# Flex.net
KiCad netlist of a schematic drawn in EAGLE
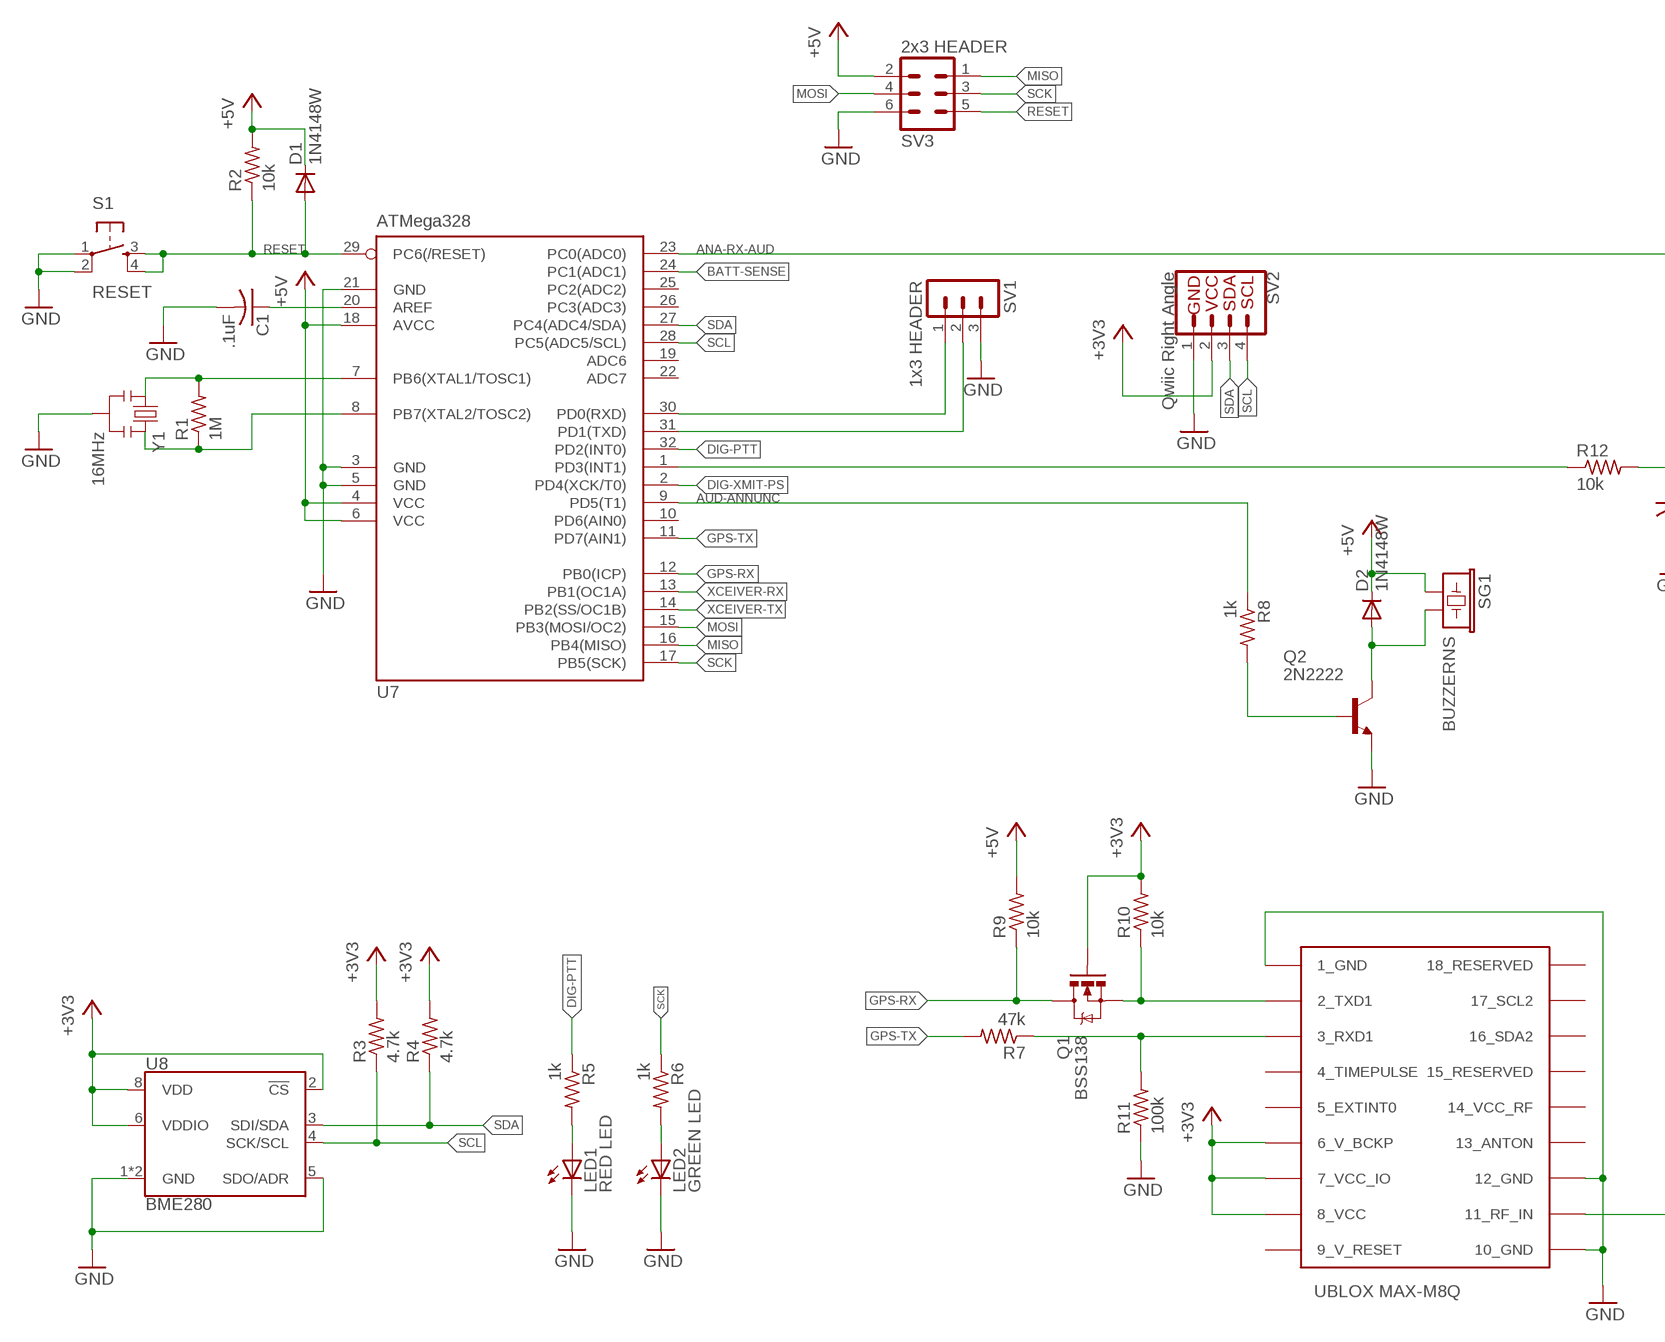
[diagram p0: schematic, sheet 1, part 1 of 2]
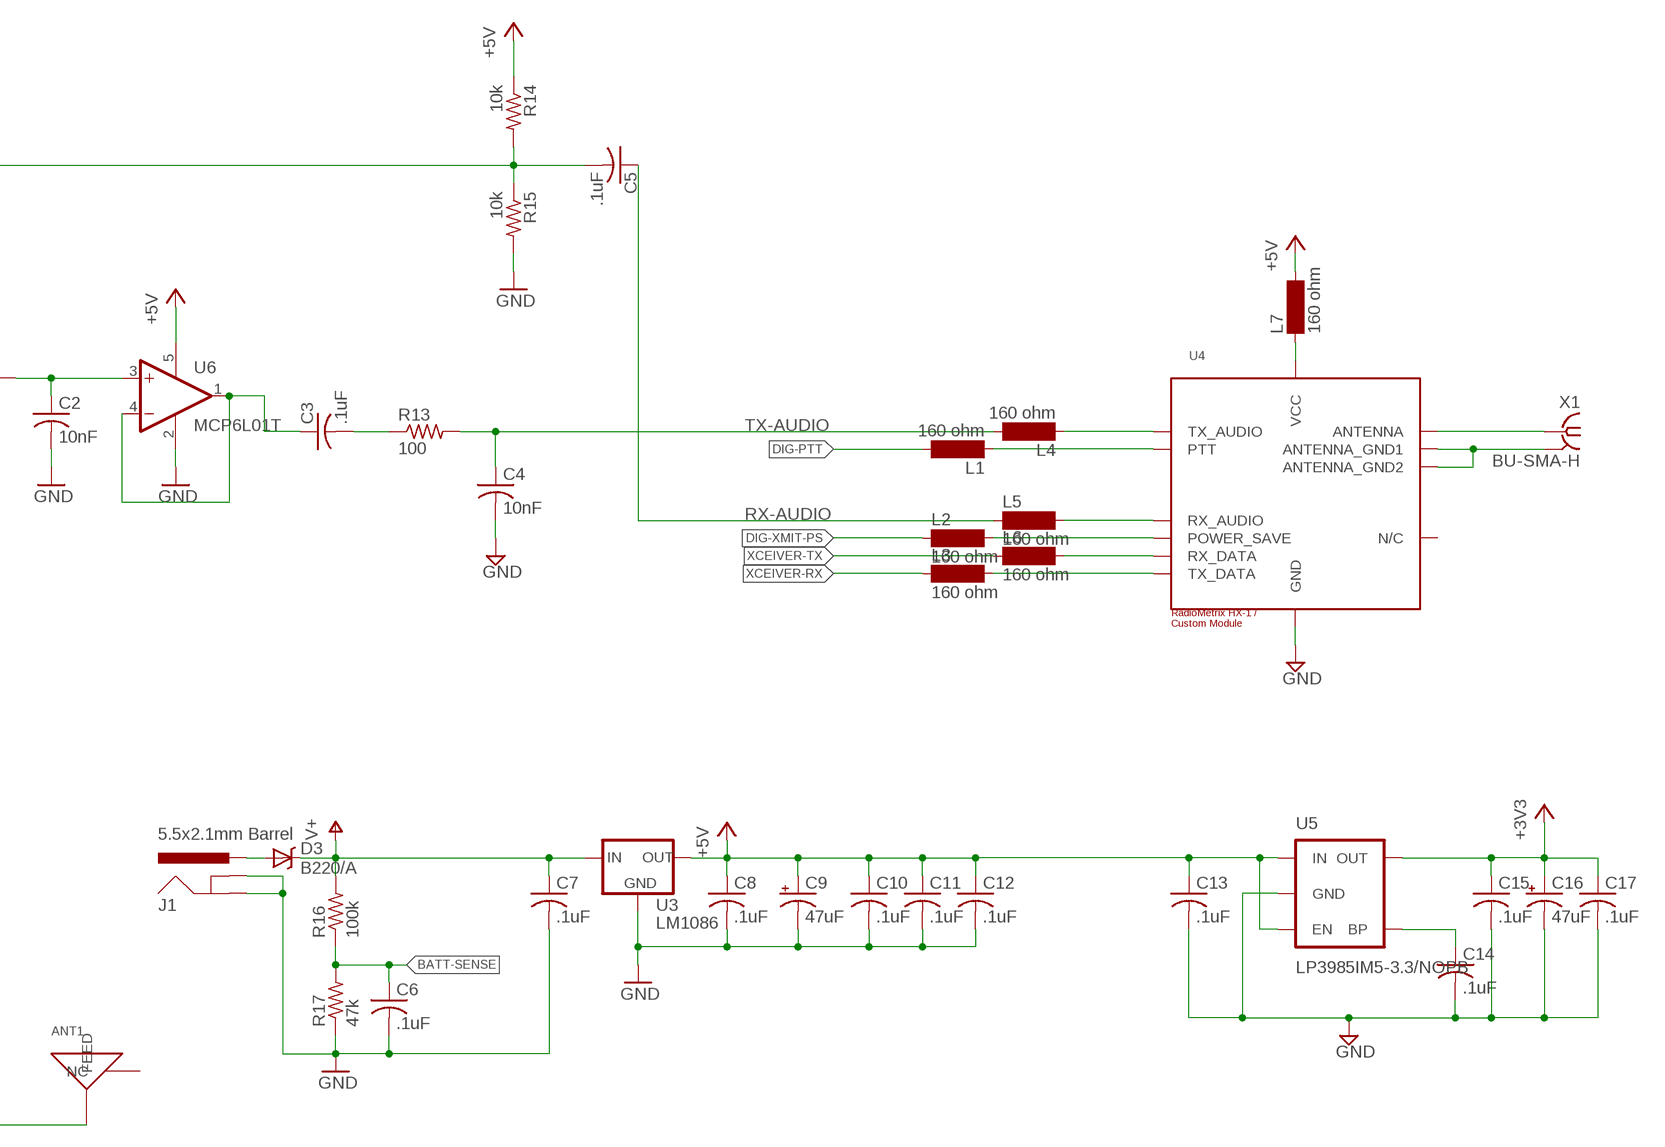
[diagram p1: schematic, sheet 1, part 2 of 2]

(export (version "E")
  (design (tool "Eeschema 10.0.6"))
  (components
    (comp (ref "ANT1")
      (value "GPS ANTENNA")
      (footprint "eagle-import:1575AT43A40")
      (libsource (lib "eagle-import") (part "GPS_ANT_SMDBAR"))
    )
    (comp (ref "C1")
      (value ".1uF")
      (footprint "eagle-import:C0805")
      (libsource (lib "eagle-import") (part "C-USC0805"))
    )
    (comp (ref "C2")
      (value "10nF")
      (footprint "eagle-import:C0805")
      (libsource (lib "eagle-import") (part "C-USC0805"))
    )
    (comp (ref "C3")
      (value ".1uF")
      (footprint "eagle-import:C0805")
      (libsource (lib "eagle-import") (part "C-USC0805"))
    )
    (comp (ref "C4")
      (value "10nF")
      (footprint "eagle-import:C0805")
      (libsource (lib "eagle-import") (part "C-USC0805"))
    )
    (comp (ref "C5")
      (value ".1uF")
      (footprint "eagle-import:C0805")
      (libsource (lib "eagle-import") (part "C-USC0805"))
    )
    (comp (ref "C6")
      (value ".1uF")
      (footprint "eagle-import:C0805")
      (libsource (lib "eagle-import") (part "C-USC0805"))
    )
    (comp (ref "C7")
      (value ".1uF")
      (footprint "eagle-import:C0805")
      (libsource (lib "eagle-import") (part "C-USC0805"))
    )
    (comp (ref "C8")
      (value ".1uF")
      (footprint "eagle-import:C0805")
      (libsource (lib "eagle-import") (part "C-USC0805"))
    )
    (comp (ref "C9")
      (value "47uF")
      (footprint "eagle-import:153CLV-0605")
      (libsource (lib "eagle-import") (part "CPOL-US153CLV-0605"))
    )
    (comp (ref "C10")
      (value ".1uF")
      (footprint "eagle-import:C0805")
      (libsource (lib "eagle-import") (part "C-USC0805"))
    )
    (comp (ref "C11")
      (value ".1uF")
      (footprint "eagle-import:C0805")
      (libsource (lib "eagle-import") (part "C-USC0805"))
    )
    (comp (ref "C12")
      (value ".1uF")
      (footprint "eagle-import:C0805")
      (libsource (lib "eagle-import") (part "C-USC0805"))
    )
    (comp (ref "C13")
      (value ".1uF")
      (footprint "eagle-import:C0805")
      (libsource (lib "eagle-import") (part "C-USC0805"))
    )
    (comp (ref "C14")
      (value ".1uF")
      (footprint "eagle-import:C0805")
      (libsource (lib "eagle-import") (part "C-USC0805"))
    )
    (comp (ref "C15")
      (value ".1uF")
      (footprint "eagle-import:C0805")
      (libsource (lib "eagle-import") (part "C-USC0805"))
    )
    (comp (ref "C16")
      (value "47uF")
      (footprint "eagle-import:153CLV-0605")
      (libsource (lib "eagle-import") (part "CPOL-US153CLV-0605"))
    )
    (comp (ref "C17")
      (value ".1uF")
      (footprint "eagle-import:C0805")
      (libsource (lib "eagle-import") (part "C-USC0805"))
    )
    (comp (ref "D1")
      (value "1N4148W")
      (footprint "eagle-import:SOD123")
      (libsource (lib "eagle-import") (part "DIODE-SOD123"))
    )
    (comp (ref "D2")
      (value "1N4148W")
      (footprint "eagle-import:SOD123")
      (libsource (lib "eagle-import") (part "DIODE-SOD123"))
    )
    (comp (ref "D3")
      (value "B220/A")
      (footprint "eagle-import:SMA-DIODE")
      (libsource (lib "eagle-import") (part "B340A"))
    )
    (comp (ref "J1")
      (value "5.5x2.1mm Barrel")
      (footprint "eagle-import:POWER_JACK_SMD")
      (libsource (lib "eagle-import") (part "POWER_JACKSMD"))
    )
    (comp (ref "L1")
      (value "160 ohm")
      (footprint "eagle-import:SM-1206")
      (libsource (lib "eagle-import") (part "SM-1206"))
    )
    (comp (ref "L2")
      (value "160 ohm")
      (footprint "eagle-import:SM-1206")
      (libsource (lib "eagle-import") (part "SM-1206"))
    )
    (comp (ref "L3")
      (value "160 ohm")
      (footprint "eagle-import:SM-1206")
      (libsource (lib "eagle-import") (part "SM-1206"))
    )
    (comp (ref "L4")
      (value "160 ohm")
      (footprint "eagle-import:SM-1206")
      (libsource (lib "eagle-import") (part "SM-1206"))
    )
    (comp (ref "L5")
      (value "160 ohm")
      (footprint "eagle-import:SM-1206")
      (libsource (lib "eagle-import") (part "SM-1206"))
    )
    (comp (ref "L6")
      (value "160 ohm")
      (footprint "eagle-import:SM-1206")
      (libsource (lib "eagle-import") (part "SM-1206"))
    )
    (comp (ref "L7")
      (value "160 ohm")
      (footprint "eagle-import:SM-1206")
      (libsource (lib "eagle-import") (part "SM-1206"))
    )
    (comp (ref "LED1")
      (value "RED LED")
      (footprint "eagle-import:CHIPLED_1206")
      (libsource (lib "eagle-import") (part "LEDCHIPLED_1206"))
    )
    (comp (ref "LED2")
      (value "GREEN LED")
      (footprint "eagle-import:CHIPLED_1206")
      (libsource (lib "eagle-import") (part "LEDCHIPLED_1206"))
    )
    (comp (ref "Q1")
      (value "BSS138")
      (footprint "eagle-import:SOT23")
      (libsource (lib "eagle-import") (part "MOSFET-NCHANNELBSS138"))
    )
    (comp (ref "Q2")
      (value "2N2222")
      (footprint "eagle-import:SOT23-BEC")
      (libsource (lib "eagle-import") (part "BC817SMD-16LT1"))
    )
    (comp (ref "R1")
      (value "1M")
      (footprint "eagle-import:R0805")
      (libsource (lib "eagle-import") (part "R-US_R0805"))
    )
    (comp (ref "R2")
      (value "10k")
      (footprint "eagle-import:R0805")
      (libsource (lib "eagle-import") (part "R-US_R0805"))
    )
    (comp (ref "R3")
      (value "4.7k")
      (footprint "eagle-import:R0805")
      (libsource (lib "eagle-import") (part "R-US_R0805"))
    )
    (comp (ref "R4")
      (value "4.7k")
      (footprint "eagle-import:R0805")
      (libsource (lib "eagle-import") (part "R-US_R0805"))
    )
    (comp (ref "R5")
      (value "1k")
      (footprint "eagle-import:R0805")
      (libsource (lib "eagle-import") (part "R-US_R0805"))
    )
    (comp (ref "R6")
      (value "1k")
      (footprint "eagle-import:R0805")
      (libsource (lib "eagle-import") (part "R-US_R0805"))
    )
    (comp (ref "R7")
      (value "47k")
      (footprint "eagle-import:R0805")
      (libsource (lib "eagle-import") (part "R-US_R0805"))
    )
    (comp (ref "R8")
      (value "1k")
      (footprint "eagle-import:R0805")
      (libsource (lib "eagle-import") (part "R-US_R0805"))
    )
    (comp (ref "R9")
      (value "10k")
      (footprint "eagle-import:R0805")
      (libsource (lib "eagle-import") (part "R-US_R0805"))
    )
    (comp (ref "R10")
      (value "10k")
      (footprint "eagle-import:R0805")
      (libsource (lib "eagle-import") (part "R-US_R0805"))
    )
    (comp (ref "R11")
      (value "100k")
      (footprint "eagle-import:R0805")
      (libsource (lib "eagle-import") (part "R-US_R0805"))
    )
    (comp (ref "R12")
      (value "10k")
      (footprint "eagle-import:R0805")
      (libsource (lib "eagle-import") (part "R-US_R0805"))
    )
    (comp (ref "R13")
      (value "100")
      (footprint "eagle-import:R0805")
      (libsource (lib "eagle-import") (part "R-US_R0805"))
    )
    (comp (ref "R14")
      (value "10k")
      (footprint "eagle-import:R0805")
      (libsource (lib "eagle-import") (part "R-US_R0805"))
    )
    (comp (ref "R15")
      (value "10k")
      (footprint "eagle-import:R0805")
      (libsource (lib "eagle-import") (part "R-US_R0805"))
    )
    (comp (ref "R16")
      (value "100k")
      (footprint "eagle-import:R0805")
      (libsource (lib "eagle-import") (part "R-US_R0805"))
    )
    (comp (ref "R17")
      (value "47k")
      (footprint "eagle-import:R0805")
      (libsource (lib "eagle-import") (part "R-US_R0805"))
    )
    (comp (ref "S1")
      (value "RESET")
      (footprint "eagle-import:TACTILE_SWITCH_SMD")
      (libsource (lib "eagle-import") (part "TAC_SWITCHSMD"))
    )
    (comp (ref "SG1")
      (value "BUZZERNS")
      (footprint "eagle-import:BUZZER-12MM-NS")
      (libsource (lib "eagle-import") (part "BUZZERNS"))
    )
    (comp (ref "SV1")
      (value "1x3 HEADER")
      (footprint "eagle-import:MA03-1")
      (libsource (lib "eagle-import") (part "MA03-1"))
    )
    (comp (ref "SV2")
      (value "Qwiic Right Angle")
      (footprint "eagle-import:1X04_1MM_RA")
      (libsource (lib "eagle-import") (part "I2C_STANDARDQWIIC"))
    )
    (comp (ref "SV3")
      (value "2x3 HEADER")
      (footprint "eagle-import:MA03-2")
      (libsource (lib "eagle-import") (part "MA03-2"))
    )
    (comp (ref "U2")
      (value "UBLOX_MAX")
      (footprint "eagle-import:UBLOX_MAX")
      (fields (field (name "ALT-PART") "UBLOX MAX-M8Q"))
      (libsource (lib "eagle-import") (part "UBLOX_MAX"))
    )
    (comp (ref "U3")
      (value "LM1086")
      (footprint "eagle-import:TO263")
      (libsource (lib "eagle-import") (part "LM1086TO263"))
    )
    (comp (ref "U4")
      (value "RADIOMETRIX-HX1-CUSTOM")
      (footprint "eagle-import:RADIOMETRIX-HX1-CUSTOM")
      (libsource (lib "eagle-import") (part "RADIOMETRIX-HX1-CUSTOM"))
    )
    (comp (ref "U5")
      (value "LP3985IM5-3.3/NOPB")
      (footprint "eagle-import:SOT23-5")
      (libsource (lib "eagle-import") (part "V_REG_LDOSMD"))
    )
    (comp (ref "U6")
      (value "MCP6L01T")
      (footprint "eagle-import:SOT23-5")
      (libsource (lib "eagle-import") (part "OPA725DBV"))
    )
    (comp (ref "U7")
      (value "ATMega328")
      (footprint "eagle-import:TQFP32-08")
      (fields (field (name "MPN") "ATMEGA8-16AU"))
      (libsource (lib "eagle-import") (part "MEGA8-AI"))
    )
    (comp (ref "U8")
      (value "BME280")
      (footprint "eagle-import:LGA-8-2.5X2.5")
      (libsource (lib "eagle-import") (part "BME280"))
    )
    (comp (ref "X1")
      (value "BU-SMA-H")
      (footprint "eagle-import:BU-SMA-H")
      (libsource (lib "eagle-import") (part "BU-SMA-H"))
    )
    (comp (ref "Y1")
      (value "16MHz")
      (footprint "eagle-import:RESONATOR-SMD")
      (libsource (lib "eagle-import") (part "RESONATOR16MHZ"))
    )
  )
  (nets
    (net (code "1") (name "+3V3") (class "Default")
      (node (ref "C15") (pin "1") (pinfunction "1_1") (pintype "passive"))
      (node (ref "C16") (pin "+") (pinfunction "+_+") (pintype "passive"))
      (node (ref "C17") (pin "1") (pinfunction "1_1") (pintype "passive"))
      (node (ref "Q1") (pin "1") (pinfunction "G_1") (pintype "passive"))
      (node (ref "R10") (pin "2") (pinfunction "2_2") (pintype "passive"))
      (node (ref "R3") (pin "2") (pinfunction "2_2") (pintype "passive"))
      (node (ref "R4") (pin "2") (pinfunction "2_2") (pintype "passive"))
      (node (ref "SV2") (pin "2") (pinfunction "2_2") (pintype "power_in"))
      (node (ref "U2") (pin "6_V_BCKP") (pinfunction "6_V_BCKP_6_V_BCKP") (pintype "bidirectional"))
      (node (ref "U2") (pin "7_VCC_IO") (pinfunction "7_VCC_IO_7_VCC_IO") (pintype "power_in"))
      (node (ref "U2") (pin "8_VCC") (pinfunction "8_VCC_8_VCC") (pintype "power_in"))
      (node (ref "U5") (pin "5") (pinfunction "OUT_5") (pintype "passive"))
      (node (ref "U8") (pin "2") (pinfunction "~{CS}_2") (pintype "bidirectional"))
      (node (ref "U8") (pin "6") (pinfunction "VDDIO_6") (pintype "bidirectional"))
      (node (ref "U8") (pin "8") (pinfunction "VDD_8") (pintype "bidirectional"))
    )
    (net (code "2") (name "+5V") (class "Default")
      (node (ref "C10") (pin "1") (pinfunction "1_1") (pintype "passive"))
      (node (ref "C11") (pin "1") (pinfunction "1_1") (pintype "passive"))
      (node (ref "C12") (pin "1") (pinfunction "1_1") (pintype "passive"))
      (node (ref "C13") (pin "1") (pinfunction "1_1") (pintype "passive"))
      (node (ref "C8") (pin "1") (pinfunction "1_1") (pintype "passive"))
      (node (ref "C9") (pin "+") (pinfunction "+_+") (pintype "passive"))
      (node (ref "D1") (pin "C") (pinfunction "C_C") (pintype "passive"))
      (node (ref "D2") (pin "C") (pinfunction "C_C") (pintype "passive"))
      (node (ref "L7") (pin "2") (pinfunction "2_2") (pintype "passive"))
      (node (ref "R14") (pin "1") (pinfunction "1_1") (pintype "passive"))
      (node (ref "R2") (pin "2") (pinfunction "2_2") (pintype "passive"))
      (node (ref "R9") (pin "2") (pinfunction "2_2") (pintype "passive"))
      (node (ref "SG1") (pin "+") (pinfunction "1_+") (pintype "passive"))
      (node (ref "SV3") (pin "2") (pinfunction "2_2") (pintype "passive"))
      (node (ref "U3") (pin "2") (pinfunction "OUT_2") (pintype "passive"))
      (node (ref "U5") (pin "1") (pinfunction "IN_1") (pintype "input"))
      (node (ref "U5") (pin "3") (pinfunction "EN_3") (pintype "input"))
      (node (ref "U6") (pin "5") (pinfunction "V+_5") (pintype "power_in"))
      (node (ref "U7") (pin "18") (pinfunction "AVCC_18") (pintype "power_in"))
      (node (ref "U7") (pin "4") (pinfunction "VCC_4") (pintype "power_in"))
      (node (ref "U7") (pin "6") (pinfunction "VCC_6") (pintype "power_in"))
    )
    (net (code "3") (name "/9_V_RESET") (class "Default")
      (node (ref "U2") (pin "9_V_RESET") (pinfunction "9_V_RESET_9_V_RESET") (pintype "power_in"))
    )
    (net (code "4") (name "/ANA-RX-AUD") (class "Default")
      (node (ref "C5") (pin "2") (pinfunction "2_2") (pintype "passive"))
      (node (ref "R14") (pin "2") (pinfunction "2_2") (pintype "passive"))
      (node (ref "R15") (pin "1") (pinfunction "1_1") (pintype "passive"))
      (node (ref "U7") (pin "23") (pinfunction "PC0(ADC0)_23") (pintype "bidirectional"))
    )
    (net (code "5") (name "/AUD-ANNUNC") (class "Default")
      (node (ref "R8") (pin "1") (pinfunction "1_1") (pintype "passive"))
      (node (ref "U7") (pin "9") (pinfunction "PD5(T1)_9") (pintype "bidirectional"))
    )
    (net (code "6") (name "/RX-AUDIO") (class "Default")
      (node (ref "C5") (pin "1") (pinfunction "1_1") (pintype "passive"))
      (node (ref "L5") (pin "1") (pinfunction "1_1") (pintype "passive"))
    )
    (net (code "7") (name "/TX-AUDIO") (class "Default")
      (node (ref "C3") (pin "2") (pinfunction "2_2") (pintype "passive"))
      (node (ref "R13") (pin "1") (pinfunction "1_1") (pintype "passive"))
    )
    (net (code "8") (name "BATT-SENSE") (class "Default")
      (node (ref "C6") (pin "1") (pinfunction "1_1") (pintype "passive"))
      (node (ref "R16") (pin "1") (pinfunction "1_1") (pintype "passive"))
      (node (ref "R17") (pin "2") (pinfunction "2_2") (pintype "passive"))
      (node (ref "U7") (pin "24") (pinfunction "PC1(ADC1)_24") (pintype "bidirectional"))
    )
    (net (code "9") (name "DIG-PTT") (class "Default")
      (node (ref "L1") (pin "2") (pinfunction "2_2") (pintype "passive"))
      (node (ref "R5") (pin "1") (pinfunction "1_1") (pintype "passive"))
      (node (ref "U7") (pin "32") (pinfunction "PD2(INT0)_32") (pintype "bidirectional"))
    )
    (net (code "10") (name "DIG-XMIT-PS") (class "Default")
      (node (ref "L2") (pin "1") (pinfunction "1_1") (pintype "passive"))
      (node (ref "U7") (pin "2") (pinfunction "PD4(XCK/T0)_2") (pintype "bidirectional"))
    )
    (net (code "11") (name "GND") (class "Default")
      (node (ref "C1") (pin "2") (pinfunction "2_2") (pintype "passive"))
      (node (ref "C10") (pin "2") (pinfunction "2_2") (pintype "passive"))
      (node (ref "C11") (pin "2") (pinfunction "2_2") (pintype "passive"))
      (node (ref "C12") (pin "2") (pinfunction "2_2") (pintype "passive"))
      (node (ref "C13") (pin "2") (pinfunction "2_2") (pintype "passive"))
      (node (ref "C14") (pin "2") (pinfunction "2_2") (pintype "passive"))
      (node (ref "C15") (pin "2") (pinfunction "2_2") (pintype "passive"))
      (node (ref "C16") (pin "-") (pinfunction "-_-") (pintype "passive"))
      (node (ref "C17") (pin "2") (pinfunction "2_2") (pintype "passive"))
      (node (ref "C2") (pin "2") (pinfunction "2_2") (pintype "passive"))
      (node (ref "C4") (pin "2") (pinfunction "2_2") (pintype "passive"))
      (node (ref "C6") (pin "2") (pinfunction "2_2") (pintype "passive"))
      (node (ref "C7") (pin "2") (pinfunction "2_2") (pintype "passive"))
      (node (ref "C8") (pin "2") (pinfunction "2_2") (pintype "passive"))
      (node (ref "C9") (pin "-") (pinfunction "-_-") (pintype "passive"))
      (node (ref "J1") (pin "GND") (pinfunction "GNDBREAK_GND") (pintype "bidirectional"))
      (node (ref "J1") (pin "P$4") (pinfunction "GND_P$4") (pintype "bidirectional"))
      (node (ref "LED1") (pin "C") (pinfunction "C_C") (pintype "passive"))
      (node (ref "LED2") (pin "C") (pinfunction "C_C") (pintype "passive"))
      (node (ref "Q2") (pin "E") (pinfunction "E_E") (pintype "passive"))
      (node (ref "R11") (pin "1") (pinfunction "1_1") (pintype "passive"))
      (node (ref "R15") (pin "2") (pinfunction "2_2") (pintype "passive"))
      (node (ref "R17") (pin "1") (pinfunction "1_1") (pintype "passive"))
      (node (ref "S1") (pin "1") (pinfunction "1_1") (pintype "passive"))
      (node (ref "S1") (pin "2") (pinfunction "2_2") (pintype "passive"))
      (node (ref "SV1") (pin "3") (pinfunction "3_3") (pintype "passive"))
      (node (ref "SV2") (pin "1") (pinfunction "1_1") (pintype "power_in"))
      (node (ref "SV3") (pin "6") (pinfunction "6_6") (pintype "passive"))
      (node (ref "U2") (pin "10_GND") (pinfunction "10_GND_10_GND") (pintype "power_in"))
      (node (ref "U2") (pin "12_GND") (pinfunction "12_GND_12_GND") (pintype "power_in"))
      (node (ref "U2") (pin "1_GND") (pinfunction "1_GND_1_GND") (pintype "power_in"))
      (node (ref "U3") (pin "1") (pinfunction "GND_1") (pintype "input"))
      (node (ref "U4") (pin "GND") (pinfunction "GND_GND") (pintype "power_in"))
      (node (ref "U5") (pin "2") (pinfunction "GND_2") (pintype "input"))
      (node (ref "U6") (pin "2") (pinfunction "V-_2") (pintype "power_in"))
      (node (ref "U7") (pin "21") (pinfunction "GND_21") (pintype "power_in"))
      (node (ref "U7") (pin "3") (pinfunction "GND_3") (pintype "power_in"))
      (node (ref "U7") (pin "5") (pinfunction "GND_5") (pintype "power_in"))
      (node (ref "U8") (pin "1") (pinfunction "GND_1") (pintype "bidirectional"))
      (node (ref "U8") (pin "5") (pinfunction "SDO/ADR_5") (pintype "bidirectional"))
      (node (ref "U8") (pin "7") (pinfunction "GND_7") (pintype "bidirectional"))
      (node (ref "Y1") (pin "2") (pinfunction "2_2") (pintype "passive"))
    )
    (net (code "12") (name "GPS-RX") (class "Default")
      (node (ref "Q1") (pin "3") (pinfunction "D_3") (pintype "passive"))
      (node (ref "R9") (pin "1") (pinfunction "1_1") (pintype "passive"))
      (node (ref "U7") (pin "12") (pinfunction "PB0(ICP)_12") (pintype "bidirectional"))
    )
    (net (code "13") (name "GPS-TX") (class "Default")
      (node (ref "R7") (pin "2") (pinfunction "2_2") (pintype "passive"))
      (node (ref "U7") (pin "11") (pinfunction "PD7(AIN1)_11") (pintype "bidirectional"))
    )
    (net (code "14") (name "MISO") (class "Default")
      (node (ref "SV3") (pin "1") (pinfunction "1_1") (pintype "passive"))
      (node (ref "U7") (pin "16") (pinfunction "PB4(MISO)_16") (pintype "bidirectional"))
    )
    (net (code "15") (name "MOSI") (class "Default")
      (node (ref "SV3") (pin "4") (pinfunction "4_4") (pintype "passive"))
      (node (ref "U7") (pin "15") (pinfunction "PB3(MOSI/OC2)_15") (pintype "bidirectional"))
    )
    (net (code "16") (name "Net-(ANT1-PadFEED)") (class "Default")
      (node (ref "ANT1") (pin "FEED") (pinfunction "FEED_FEED") (pintype "bidirectional"))
      (node (ref "U2") (pin "11_RF_IN") (pinfunction "11_RF_IN_11_RF_IN") (pintype "bidirectional"))
    )
    (net (code "17") (name "Net-(C4-Pad1)") (class "Default")
      (node (ref "C4") (pin "1") (pinfunction "1_1") (pintype "passive"))
      (node (ref "L4") (pin "2") (pinfunction "2_2") (pintype "passive"))
      (node (ref "R13") (pin "2") (pinfunction "2_2") (pintype "passive"))
    )
    (net (code "18") (name "Net-(J1-PWR)") (class "Default")
      (node (ref "D3") (pin "A") (pinfunction "A_A") (pintype "passive"))
      (node (ref "J1") (pin "VIN0") (pinfunction "PWR_VIN0") (pintype "bidirectional"))
    )
    (net (code "19") (name "Net-(L1-Pad1)") (class "Default")
      (node (ref "L1") (pin "1") (pinfunction "1_1") (pintype "passive"))
      (node (ref "U4") (pin "PTT") (pinfunction "PTT_PTT") (pintype "input"))
    )
    (net (code "20") (name "Net-(L2-Pad2)") (class "Default")
      (node (ref "L2") (pin "2") (pinfunction "2_2") (pintype "passive"))
      (node (ref "U4") (pin "POWER_SAVE") (pinfunction "POWER_SAVE_POWER_SAVE") (pintype "input"))
    )
    (net (code "21") (name "Net-(L3-Pad2)") (class "Default")
      (node (ref "L3") (pin "2") (pinfunction "2_2") (pintype "passive"))
      (node (ref "U4") (pin "TX_DATA") (pinfunction "TX_DATA_TX_DATA") (pintype "output"))
    )
    (net (code "22") (name "Net-(L4-Pad1)") (class "Default")
      (node (ref "L4") (pin "1") (pinfunction "1_1") (pintype "passive"))
      (node (ref "U4") (pin "TX_AUDIO") (pinfunction "TX_AUDIO_TX_AUDIO") (pintype "input"))
    )
    (net (code "23") (name "Net-(L5-Pad2)") (class "Default")
      (node (ref "L5") (pin "2") (pinfunction "2_2") (pintype "passive"))
      (node (ref "U4") (pin "RX_AUDIO") (pinfunction "RX_AUDIO_RX_AUDIO") (pintype "output"))
    )
    (net (code "24") (name "Net-(L6-Pad2)") (class "Default")
      (node (ref "L6") (pin "2") (pinfunction "2_2") (pintype "passive"))
      (node (ref "U4") (pin "RX_DATA") (pinfunction "RX_DATA_RX_DATA") (pintype "input"))
    )
    (net (code "25") (name "Net-(L7-Pad1)") (class "Default")
      (node (ref "L7") (pin "1") (pinfunction "1_1") (pintype "passive"))
      (node (ref "U4") (pin "VCC") (pinfunction "VCC_VCC") (pintype "power_in"))
    )
    (net (code "26") (name "Net-(LED1-PadA)") (class "Default")
      (node (ref "LED1") (pin "A") (pinfunction "A_A") (pintype "passive"))
      (node (ref "R5") (pin "2") (pinfunction "2_2") (pintype "passive"))
    )
    (net (code "27") (name "Net-(LED2-PadA)") (class "Default")
      (node (ref "LED2") (pin "A") (pinfunction "A_A") (pintype "passive"))
      (node (ref "R6") (pin "2") (pinfunction "2_2") (pintype "passive"))
    )
    (net (code "28") (name "Net-(Q1-S)") (class "Default")
      (node (ref "Q1") (pin "2") (pinfunction "S_2") (pintype "passive"))
      (node (ref "R10") (pin "1") (pinfunction "1_1") (pintype "passive"))
      (node (ref "U2") (pin "2_TXD1") (pinfunction "2_TXD1_2_TXD1") (pintype "bidirectional"))
    )
    (net (code "29") (name "Net-(Q2-PadB)") (class "Default")
      (node (ref "Q2") (pin "B") (pinfunction "B_B") (pintype "passive"))
      (node (ref "R8") (pin "2") (pinfunction "2_2") (pintype "passive"))
    )
    (net (code "30") (name "Net-(R11-Pad2)") (class "Default")
      (node (ref "R11") (pin "2") (pinfunction "2_2") (pintype "passive"))
      (node (ref "R7") (pin "1") (pinfunction "1_1") (pintype "passive"))
      (node (ref "U2") (pin "3_RXD1") (pinfunction "3_RXD1_3_RXD1") (pintype "bidirectional"))
    )
    (net (code "31") (name "Net-(SG1-2)") (class "Default")
      (node (ref "D2") (pin "A") (pinfunction "A_A") (pintype "passive"))
      (node (ref "Q2") (pin "C") (pinfunction "C_C") (pintype "passive"))
      (node (ref "SG1") (pin "-") (pinfunction "2_-") (pintype "passive"))
    )
    (net (code "32") (name "Net-(U4-PadANTENNA)") (class "Default")
      (node (ref "U4") (pin "ANTENNA") (pinfunction "ANTENNA_ANTENNA") (pintype "bidirectional"))
      (node (ref "X1") (pin "1") (pinfunction "1_1") (pintype "passive"))
    )
    (net (code "33") (name "Net-(U4-PadANTENNA_GND1)") (class "Default")
      (node (ref "U4") (pin "ANTENNA_GND1") (pinfunction "ANTENNA_GND1_ANTENNA_GND1") (pintype "bidirectional"))
      (node (ref "U4") (pin "ANTENNA_GND2") (pinfunction "ANTENNA_GND2_ANTENNA_GND2") (pintype "bidirectional"))
      (node (ref "X1") (pin "2") (pinfunction "2_2") (pintype "passive"))
      (node (ref "X1") (pin "3") (pinfunction "2_3") (pintype "passive"))
      (node (ref "X1") (pin "4") (pinfunction "2_4") (pintype "passive"))
      (node (ref "X1") (pin "5") (pinfunction "2_5") (pintype "passive"))
    )
    (net (code "34") (name "Net-(U5-BP)") (class "Default")
      (node (ref "C14") (pin "1") (pinfunction "1_1") (pintype "passive"))
      (node (ref "U5") (pin "4") (pinfunction "BP_4") (pintype "input"))
    )
    (net (code "35") (name "Net-(U6-+IN)") (class "Default")
      (node (ref "C2") (pin "1") (pinfunction "1_1") (pintype "passive"))
      (node (ref "R12") (pin "2") (pinfunction "2_2") (pintype "passive"))
      (node (ref "U6") (pin "3") (pinfunction "+IN_3") (pintype "input"))
    )
    (net (code "36") (name "Net-(U6--IN)") (class "Default")
      (node (ref "C3") (pin "1") (pinfunction "1_1") (pintype "passive"))
      (node (ref "U6") (pin "1") (pinfunction "OUT_1") (pintype "output"))
      (node (ref "U6") (pin "4") (pinfunction "-IN_4") (pintype "input"))
    )
    (net (code "37") (name "Net-(U7-AREF)") (class "Default")
      (node (ref "C1") (pin "1") (pinfunction "1_1") (pintype "passive"))
      (node (ref "U7") (pin "20") (pinfunction "AREF_20") (pintype "passive"))
    )
    (net (code "38") (name "Net-(U7-PB6(XTAL1{slash}TOSC1))") (class "Default")
      (node (ref "R1") (pin "2") (pinfunction "2_2") (pintype "passive"))
      (node (ref "U7") (pin "7") (pinfunction "PB6(XTAL1/TOSC1)_7") (pintype "bidirectional"))
      (node (ref "Y1") (pin "1") (pinfunction "1_1") (pintype "passive"))
    )
    (net (code "39") (name "Net-(U7-PB7(XTAL2{slash}TOSC2))") (class "Default")
      (node (ref "R1") (pin "1") (pinfunction "1_1") (pintype "passive"))
      (node (ref "U7") (pin "8") (pinfunction "PB7(XTAL2/TOSC2)_8") (pintype "bidirectional"))
      (node (ref "Y1") (pin "3") (pinfunction "3_3") (pintype "passive"))
    )
    (net (code "40") (name "Net-(U7-PD0(RXD))") (class "Default")
      (node (ref "SV1") (pin "1") (pinfunction "1_1") (pintype "passive"))
      (node (ref "U7") (pin "30") (pinfunction "PD0(RXD)_30") (pintype "bidirectional"))
    )
    (net (code "41") (name "Net-(U7-PD1(TXD))") (class "Default")
      (node (ref "SV1") (pin "2") (pinfunction "2_2") (pintype "passive"))
      (node (ref "U7") (pin "31") (pinfunction "PD1(TXD)_31") (pintype "bidirectional"))
    )
    (net (code "42") (name "Net-(U7-PD3(INT1))") (class "Default")
      (node (ref "R12") (pin "1") (pinfunction "1_1") (pintype "passive"))
      (node (ref "U7") (pin "1") (pinfunction "PD3(INT1)_1") (pintype "bidirectional"))
    )
    (net (code "43") (name "RESET") (class "Default")
      (node (ref "D1") (pin "A") (pinfunction "A_A") (pintype "passive"))
      (node (ref "R2") (pin "1") (pinfunction "1_1") (pintype "passive"))
      (node (ref "S1") (pin "3") (pinfunction "3_3") (pintype "passive"))
      (node (ref "S1") (pin "4") (pinfunction "4_4") (pintype "passive"))
      (node (ref "SV3") (pin "5") (pinfunction "5_5") (pintype "passive"))
      (node (ref "U7") (pin "29") (pinfunction "PC6(/RESET)_29") (pintype "bidirectional"))
    )
    (net (code "44") (name "SCK") (class "Default")
      (node (ref "R6") (pin "1") (pinfunction "1_1") (pintype "passive"))
      (node (ref "SV3") (pin "3") (pinfunction "3_3") (pintype "passive"))
      (node (ref "U7") (pin "17") (pinfunction "PB5(SCK)_17") (pintype "bidirectional"))
    )
    (net (code "45") (name "SCL") (class "Default")
      (node (ref "R3") (pin "1") (pinfunction "1_1") (pintype "passive"))
      (node (ref "SV2") (pin "4") (pinfunction "4_4") (pintype "passive"))
      (node (ref "U7") (pin "28") (pinfunction "PC5(ADC5/SCL)_28") (pintype "bidirectional"))
      (node (ref "U8") (pin "4") (pinfunction "SCK/SCL_4") (pintype "bidirectional"))
    )
    (net (code "46") (name "SDA") (class "Default")
      (node (ref "R4") (pin "1") (pinfunction "1_1") (pintype "passive"))
      (node (ref "SV2") (pin "3") (pinfunction "3_3") (pintype "passive"))
      (node (ref "U7") (pin "27") (pinfunction "PC4(ADC4/SDA)_27") (pintype "bidirectional"))
      (node (ref "U8") (pin "3") (pinfunction "SDI/SDA_3") (pintype "bidirectional"))
    )
    (net (code "47") (name "V+") (class "Default")
      (node (ref "C7") (pin "1") (pinfunction "1_1") (pintype "passive"))
      (node (ref "D3") (pin "C") (pinfunction "C_C") (pintype "passive"))
      (node (ref "R16") (pin "2") (pinfunction "2_2") (pintype "passive"))
      (node (ref "U3") (pin "3") (pinfunction "IN_3") (pintype "input"))
    )
    (net (code "48") (name "XCEIVER-RX") (class "Default")
      (node (ref "L3") (pin "1") (pinfunction "1_1") (pintype "passive"))
      (node (ref "U7") (pin "13") (pinfunction "PB1(OC1A)_13") (pintype "bidirectional"))
    )
    (net (code "49") (name "XCEIVER-TX") (class "Default")
      (node (ref "L6") (pin "1") (pinfunction "1_1") (pintype "passive"))
      (node (ref "U7") (pin "14") (pinfunction "PB2(SS/OC1B)_14") (pintype "bidirectional"))
    )
    (net (code "50") (name "unconnected-(ANT1-PadNC)") (class "Default")
      (node (ref "ANT1") (pin "NC") (pinfunction "NC_NC") (pintype "bidirectional"))
    )
    (net (code "51") (name "unconnected-(U2-Pad4_TIMEPULSE)") (class "Default")
      (node (ref "U2") (pin "4_TIMEPULSE") (pinfunction "4_TIMEPULSE_4_TIMEPULSE") (pintype "bidirectional"))
    )
    (net (code "52") (name "unconnected-(U2-Pad5_EXTINT0)") (class "Default")
      (node (ref "U2") (pin "5_EXTINT0") (pinfunction "5_EXTINT0_5_EXTINT0") (pintype "bidirectional"))
    )
    (net (code "53") (name "unconnected-(U2-Pad13_ANTON)") (class "Default")
      (node (ref "U2") (pin "13_ANTON") (pinfunction "13_ANTON_13_ANTON") (pintype "bidirectional"))
    )
    (net (code "54") (name "unconnected-(U2-Pad14_VCC_RF)") (class "Default")
      (node (ref "U2") (pin "14_VCC_RF") (pinfunction "14_VCC_RF_14_VCC_RF") (pintype "bidirectional"))
    )
    (net (code "55") (name "unconnected-(U2-Pad15_RESERVED)") (class "Default")
      (node (ref "U2") (pin "15_RESERVED") (pinfunction "15_RESERVED_15_RESERVED") (pintype "bidirectional"))
    )
    (net (code "56") (name "unconnected-(U2-Pad16_SDA2)") (class "Default")
      (node (ref "U2") (pin "16_SDA2") (pinfunction "16_SDA2_16_SDA2") (pintype "bidirectional"))
    )
    (net (code "57") (name "unconnected-(U2-Pad17_SCL2)") (class "Default")
      (node (ref "U2") (pin "17_SCL2") (pinfunction "17_SCL2_17_SCL2") (pintype "bidirectional"))
    )
    (net (code "58") (name "unconnected-(U2-Pad18_RESERVED)") (class "Default")
      (node (ref "U2") (pin "18_RESERVED") (pinfunction "18_RESERVED_18_RESERVED") (pintype "bidirectional"))
    )
    (net (code "59") (name "unconnected-(U4-N{slash}C-PadN{slash}C1)") (class "Default")
      (node (ref "U4") (pin "N/C1") (pinfunction "N/C_N/C1") (pintype "no_connect"))
    )
    (net (code "60") (name "unconnected-(U4-N{slash}C-PadN{slash}C2)") (class "Default")
      (node (ref "U4") (pin "N/C2") (pinfunction "N/C_N/C2") (pintype "no_connect"))
    )
    (net (code "61") (name "unconnected-(U4-N{slash}C-PadN{slash}C3)") (class "Default")
      (node (ref "U4") (pin "N/C3") (pinfunction "N/C_N/C3") (pintype "no_connect"))
    )
    (net (code "62") (name "unconnected-(U4-N{slash}C-PadN{slash}C4)") (class "Default")
      (node (ref "U4") (pin "N/C4") (pinfunction "N/C_N/C4") (pintype "no_connect"))
    )
    (net (code "63") (name "unconnected-(U7-ADC6-Pad19)") (class "Default")
      (node (ref "U7") (pin "19") (pinfunction "ADC6_19") (pintype "bidirectional"))
    )
    (net (code "64") (name "unconnected-(U7-ADC7-Pad22)") (class "Default")
      (node (ref "U7") (pin "22") (pinfunction "ADC7_22") (pintype "bidirectional"))
    )
    (net (code "65") (name "unconnected-(U7-PC2(ADC2)-Pad25)") (class "Default")
      (node (ref "U7") (pin "25") (pinfunction "PC2(ADC2)_25") (pintype "bidirectional"))
    )
    (net (code "66") (name "unconnected-(U7-PC3(ADC3)-Pad26)") (class "Default")
      (node (ref "U7") (pin "26") (pinfunction "PC3(ADC3)_26") (pintype "bidirectional"))
    )
    (net (code "67") (name "unconnected-(U7-PD6(AIN0)-Pad10)") (class "Default")
      (node (ref "U7") (pin "10") (pinfunction "PD6(AIN0)_10") (pintype "bidirectional"))
    )
  )
)
